# ST_LINK.net
KiCad netlist of a schematic drawn in Altium Designer
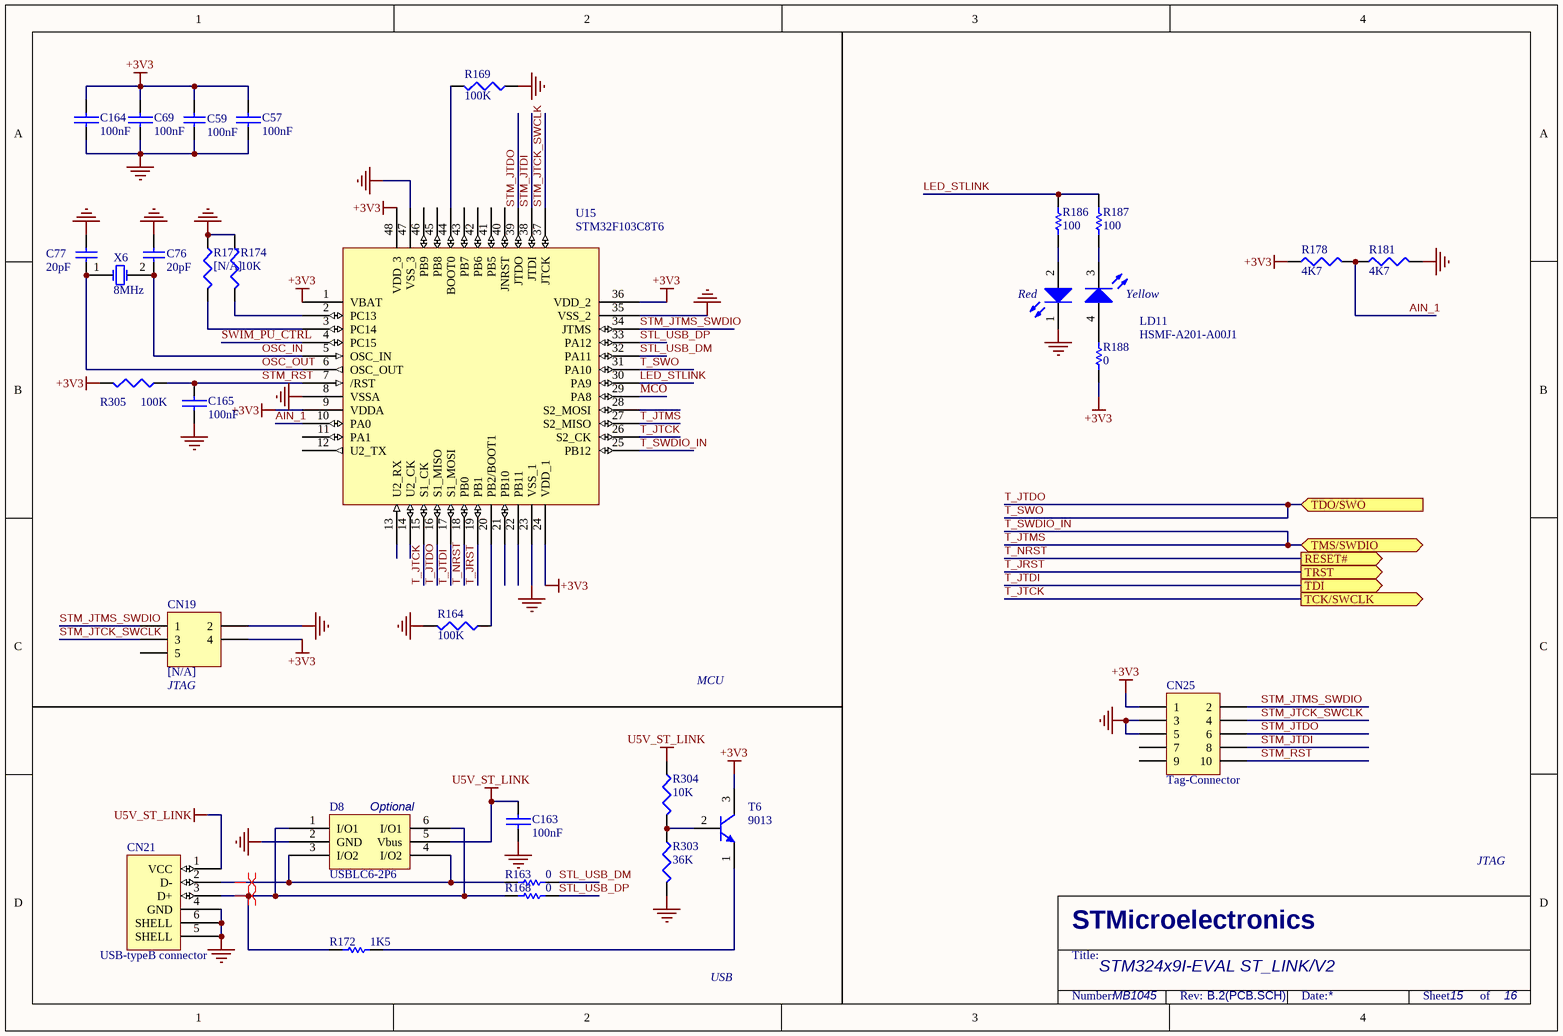
[diagram p0: ST_LINK.SCHDOC]

(export (version "E")
  (design (tool "Eeschema 10.0.6"))
  (components
    (comp (ref "C57") (value "100nF") (footprint "0603C") (libsource (lib "*") (part "CAP")))
    (comp (ref "C59")
      (value "100nF")
      (footprint "0603C")
      (description "Capacitor")
      (fields (field (name "PUBLISHER") "Altium Limited"))
      (libsource (lib "*") (part "Cap"))
    )
    (comp (ref "C69") (value "100nF") (footprint "0603C") (libsource (lib "*") (part "CAP")))
    (comp (ref "C76")
      (value "20pF")
      (footprint "0603C")
      (description "Capacitor")
      (fields (field (name "PUBLISHER") "Altium Limited"))
      (libsource (lib "*") (part "Cap"))
    )
    (comp (ref "C77")
      (value "20pF")
      (footprint "0603C")
      (description "Capacitor")
      (fields (field (name "PUBLISHER") "Altium Limited"))
      (libsource (lib "*") (part "Cap"))
    )
    (comp (ref "C163")
      (value "100nF")
      (footprint "0603C")
      (description "Capacitor")
      (libsource (lib "") (part "CAP_1"))
    )
    (comp (ref "C164") (value "100nF") (footprint "0603C") (libsource (lib "*") (part "CAP")))
    (comp (ref "C165") (value "100nF") (footprint "0603C") (libsource (lib "*") (part "CAP")))
    (comp (ref "CN19")
      (value "[N/A]")
      (footprint "HDR_2X3-1_2R54-6")
      (description "Header, 3-Pin, Dual row")
      (fields (field (name "PUBLISHER") "Altium Limited"))
      (libsource (lib "Miscellaneous Connectors") (part "Header 3X2"))
    )
    (comp (ref "CN21")
      (value "USB-typeB connector")
      (footprint "USB-B")
      (libsource (lib "mb1045") (part "USB-typeB connector"))
    )
    (comp (ref "CN25")
      (value "Tag-Connector")
      (footprint "TC2050-IDC-FP")
      (description "Header, 6-Pin, Dual row")
      (fields (field (name "PUBLISHER") "Altium Limited"))
      (libsource (lib "mb1045") (part "Tag-Connector"))
    )
    (comp (ref "D8") (value "USBLC6-2P6") (footprint "SOT-563") (libsource (lib "mb1045") (part "USBLC6-2")))
    (comp (ref "LD11")
      (value "HSMF-A201-A00J1")
      (footprint "LED2_3528")
      (libsource (lib "MB819") (part "HSMF-A201-A00J1"))
    )
    (comp (ref "R163")
      (value "0")
      (footprint "0603R")
      (description "Resistor")
      (fields (field (name "PUBLISHER") "Altium Limited"))
      (libsource (lib "Miscellaneous Devices") (part "Res1"))
    )
    (comp (ref "R164") (value "100K") (footprint "0603R") (libsource (lib "*") (part "RES1")))
    (comp (ref "R168")
      (value "0")
      (footprint "0603R")
      (description "Resistor")
      (fields (field (name "PUBLISHER") "Altium Limited"))
      (libsource (lib "Miscellaneous Devices") (part "Res1"))
    )
    (comp (ref "R169") (value "100K") (footprint "0603R") (libsource (lib "*") (part "RES1")))
    (comp (ref "R172")
      (value "1K5")
      (footprint "0603R")
      (description "Resistor")
      (fields (field (name "PUBLISHER") "Altium Limited"))
      (libsource (lib "Miscellaneous Devices") (part "Res1"))
    )
    (comp (ref "R174") (value "10K") (footprint "0603R") (libsource (lib "*") (part "R")))
    (comp (ref "R177") (value "[N/A]") (footprint "0603R") (libsource (lib "*") (part "R")))
    (comp (ref "R178") (value "4K7") (footprint "0603R") (libsource (lib "*") (part "RES1")))
    (comp (ref "R181") (value "4K7") (footprint "0603R") (libsource (lib "*") (part "RES1")))
    (comp (ref "R186")
      (value "100")
      (footprint "0603R")
      (description "Resistor")
      (fields (field (name "PUBLISHER") "Altium Limited"))
      (libsource (lib "Miscellaneous Devices") (part "Res1"))
    )
    (comp (ref "R187")
      (value "100")
      (footprint "0603R")
      (description "Resistor")
      (fields (field (name "PUBLISHER") "Altium Limited"))
      (libsource (lib "Miscellaneous Devices") (part "Res1"))
    )
    (comp (ref "R188")
      (value "0")
      (footprint "0603R")
      (description "Resistor")
      (fields (field (name "PUBLISHER") "Altium Limited"))
      (libsource (lib "Miscellaneous Devices") (part "Res1"))
    )
    (comp (ref "R303") (value "36K") (footprint "0603R") (libsource (lib "*") (part "R")))
    (comp (ref "R304") (value "10K") (footprint "0603R") (libsource (lib "*") (part "R")))
    (comp (ref "R305") (value "100K") (footprint "0603R") (libsource (lib "*") (part "RES1")))
    (comp (ref "T6")
      (value "9013")
      (footprint "SOT23-213")
      (description "NPN Bipolar Transistor")
      (fields (field (name "PUBLISHER") "Altium Limited"))
      (libsource (lib "mb1045") (part "NPN"))
    )
    (comp (ref "U15")
      (value "STM32F103C8T6")
      (footprint "LQFP48_0R5_9X9")
      (libsource (lib "*") (part "STM32F10x(48pin)"))
    )
    (comp (ref "X6")
      (value "8MHz")
      (footprint "XTAL_2SM_12R7X4R7")
      (description "Crystal Oscillator")
      (fields (field (name "PUBLISHER") "Altium Limited"))
      (libsource (lib "*") (part "XTAL"))
    )
  )
  (nets
    (net (code "1") (name "+3V3") (class "Default")
      (node (ref "C164") (pin "2") (pinfunction "2_2") (pintype "passive"))
      (node (ref "C57") (pin "2") (pinfunction "2_2") (pintype "passive"))
      (node (ref "C59") (pin "1") (pinfunction "1_1") (pintype "passive"))
      (node (ref "C69") (pin "2") (pinfunction "2_2") (pintype "passive"))
      (node (ref "CN19") (pin "4") (pinfunction "4_4") (pintype "passive"))
      (node (ref "CN25") (pin "1") (pinfunction "1_1") (pintype "passive"))
      (node (ref "R178") (pin "1") (pinfunction "1_1") (pintype "passive"))
      (node (ref "R188") (pin "2") (pinfunction "2_2") (pintype "passive"))
      (node (ref "R305") (pin "2") (pinfunction "2_2") (pintype "passive"))
      (node (ref "T6") (pin "3") (pinfunction "C_3") (pintype "passive"))
      (node (ref "U15") (pin "1") (pinfunction "VBAT_1") (pintype "power_in"))
      (node (ref "U15") (pin "24") (pinfunction "VDD_1_24") (pintype "power_in"))
      (node (ref "U15") (pin "36") (pinfunction "VDD_2_36") (pintype "power_in"))
      (node (ref "U15") (pin "48") (pinfunction "VDD_3_48") (pintype "power_in"))
      (node (ref "U15") (pin "9") (pinfunction "VDDA_9") (pintype "power_in"))
    )
    (net (code "2") (name "/AIN_1") (class "Default")
      (node (ref "R178") (pin "2") (pinfunction "2_2") (pintype "passive"))
      (node (ref "R181") (pin "1") (pinfunction "1_1") (pintype "passive"))
      (node (ref "U15") (pin "10") (pinfunction "PA0_10") (pintype "bidirectional"))
    )
    (net (code "3") (name "/LED_STLINK") (class "Default")
      (node (ref "R186") (pin "1") (pinfunction "1_1") (pintype "passive"))
      (node (ref "R187") (pin "1") (pinfunction "1_1") (pintype "passive"))
      (node (ref "U15") (pin "30") (pinfunction "PA9_30") (pintype "bidirectional"))
    )
    (net (code "4") (name "/MCO") (class "Default")
      (node (ref "U15") (pin "29") (pinfunction "PA8_29") (pintype "bidirectional"))
    )
    (net (code "5") (name "/OSC_IN") (class "Default")
      (node (ref "C76") (pin "2") (pinfunction "2_2") (pintype "passive"))
      (node (ref "U15") (pin "5") (pinfunction "OSC_IN_5") (pintype "input"))
      (node (ref "X6") (pin "2") (pinfunction "OSC2_2") (pintype "passive"))
    )
    (net (code "6") (name "/OSC_OUT") (class "Default")
      (node (ref "C77") (pin "2") (pinfunction "2_2") (pintype "passive"))
      (node (ref "U15") (pin "6") (pinfunction "OSC_OUT_6") (pintype "output"))
      (node (ref "X6") (pin "1") (pinfunction "OSC1_1") (pintype "passive"))
    )
    (net (code "7") (name "/STL_USB_DM") (class "Default")
      (node (ref "R163") (pin "1") (pinfunction "1_1") (pintype "passive"))
      (node (ref "U15") (pin "32") (pinfunction "PA11_32") (pintype "bidirectional"))
    )
    (net (code "8") (name "/STL_USB_DP") (class "Default")
      (node (ref "R168") (pin "1") (pinfunction "1_1") (pintype "passive"))
      (node (ref "U15") (pin "33") (pinfunction "PA12_33") (pintype "bidirectional"))
    )
    (net (code "9") (name "/STM_JTCK_SWCLK") (class "Default")
      (node (ref "CN19") (pin "3") (pinfunction "3_3") (pintype "passive"))
      (node (ref "CN25") (pin "4") (pinfunction "4_4") (pintype "passive"))
      (node (ref "U15") (pin "37") (pinfunction "JTCK_37") (pintype "bidirectional"))
    )
    (net (code "10") (name "/STM_JTDI") (class "Default")
      (node (ref "CN25") (pin "8") (pinfunction "8_8") (pintype "passive"))
      (node (ref "U15") (pin "38") (pinfunction "JTDI_38") (pintype "bidirectional"))
    )
    (net (code "11") (name "/STM_JTDO") (class "Default")
      (node (ref "CN25") (pin "6") (pinfunction "6_6") (pintype "passive"))
      (node (ref "U15") (pin "39") (pinfunction "JTDO_39") (pintype "bidirectional"))
    )
    (net (code "12") (name "/STM_JTMS_SWDIO") (class "Default")
      (node (ref "CN19") (pin "1") (pinfunction "1_1") (pintype "passive"))
      (node (ref "CN25") (pin "2") (pinfunction "2_2") (pintype "passive"))
      (node (ref "U15") (pin "34") (pinfunction "JTMS_34") (pintype "bidirectional"))
    )
    (net (code "13") (name "/STM_RST") (class "Default")
      (node (ref "C165") (pin "2") (pinfunction "2_2") (pintype "passive"))
      (node (ref "CN25") (pin "10") (pinfunction "10_10") (pintype "passive"))
      (node (ref "R305") (pin "1") (pinfunction "1_1") (pintype "passive"))
      (node (ref "U15") (pin "7") (pinfunction "/RST_7") (pintype "input"))
    )
    (net (code "14") (name "/SWIM_PU_CTRL") (class "Default")
      (node (ref "U15") (pin "4") (pinfunction "PC15_4") (pintype "bidirectional"))
    )
    (net (code "15") (name "/T_JRST") (class "Default")
      (node (ref "U15") (pin "19") (pinfunction "PB1_19") (pintype "bidirectional"))
    )
    (net (code "16") (name "/T_JTCK") (class "Default")
      (node (ref "U15") (pin "15") (pinfunction "S1_CK_15") (pintype "bidirectional"))
      (node (ref "U15") (pin "26") (pinfunction "S2_CK_26") (pintype "bidirectional"))
    )
    (net (code "17") (name "/T_JTDI") (class "Default")
      (node (ref "U15") (pin "17") (pinfunction "S1_MOSI_17") (pintype "bidirectional"))
    )
    (net (code "18") (name "/T_JTDO") (class "Default")
      (node (ref "U15") (pin "16") (pinfunction "S1_MISO_16") (pintype "bidirectional"))
      (node (ref "U15") (pin "31") (pinfunction "PA10_31") (pintype "bidirectional"))
    )
    (net (code "19") (name "/T_JTMS") (class "Default")
      (node (ref "U15") (pin "25") (pinfunction "PB12_25") (pintype "bidirectional"))
      (node (ref "U15") (pin "27") (pinfunction "S2_MISO_27") (pintype "bidirectional"))
    )
    (net (code "20") (name "/T_NRST") (class "Default")
      (node (ref "U15") (pin "18") (pinfunction "PB0_18") (pintype "bidirectional"))
    )
    (net (code "21") (name "GND") (class "Default")
      (node (ref "C163") (pin "2") (pinfunction "2_2") (pintype "passive"))
      (node (ref "C164") (pin "1") (pinfunction "1_1") (pintype "passive"))
      (node (ref "C165") (pin "1") (pinfunction "1_1") (pintype "passive"))
      (node (ref "C57") (pin "1") (pinfunction "1_1") (pintype "passive"))
      (node (ref "C59") (pin "2") (pinfunction "2_2") (pintype "passive"))
      (node (ref "C69") (pin "1") (pinfunction "1_1") (pintype "passive"))
      (node (ref "C76") (pin "1") (pinfunction "1_1") (pintype "passive"))
      (node (ref "C77") (pin "1") (pinfunction "1_1") (pintype "passive"))
      (node (ref "CN19") (pin "2") (pinfunction "2_2") (pintype "passive"))
      (node (ref "CN21") (pin "4") (pinfunction "GND_4") (pintype "passive"))
      (node (ref "CN21") (pin "5") (pinfunction "SHELL_5") (pintype "power_in"))
      (node (ref "CN21") (pin "6") (pinfunction "SHELL_6") (pintype "power_in"))
      (node (ref "CN25") (pin "3") (pinfunction "3_3") (pintype "passive"))
      (node (ref "CN25") (pin "5") (pinfunction "5_5") (pintype "passive"))
      (node (ref "D8") (pin "2") (pinfunction "GND_2") (pintype "passive"))
      (node (ref "LD11") (pin "1") (pinfunction "RED_cathode_1") (pintype "passive"))
      (node (ref "R164") (pin "2") (pinfunction "2_2") (pintype "passive"))
      (node (ref "R169") (pin "1") (pinfunction "1_1") (pintype "passive"))
      (node (ref "R174") (pin "1") (pinfunction "1_1") (pintype "passive"))
      (node (ref "R177") (pin "1") (pinfunction "1_1") (pintype "passive"))
      (node (ref "R181") (pin "2") (pinfunction "2_2") (pintype "passive"))
      (node (ref "R303") (pin "2") (pinfunction "2_2") (pintype "passive"))
      (node (ref "U15") (pin "23") (pinfunction "VSS_1_23") (pintype "passive"))
      (node (ref "U15") (pin "35") (pinfunction "VSS_2_35") (pintype "passive"))
      (node (ref "U15") (pin "47") (pinfunction "VSS_3_47") (pintype "passive"))
      (node (ref "U15") (pin "8") (pinfunction "VSSA_8") (pintype "passive"))
    )
    (net (code "22") (name "Net-(CN21-D+)") (class "Default")
      (node (ref "CN21") (pin "3") (pinfunction "D+_3") (pintype "bidirectional"))
      (node (ref "D8") (pin "1") (pinfunction "I/O1_1") (pintype "passive"))
      (node (ref "D8") (pin "6") (pinfunction "I/O1_6") (pintype "passive"))
      (node (ref "R168") (pin "2") (pinfunction "2_2") (pintype "passive"))
      (node (ref "R172") (pin "2") (pinfunction "2_2") (pintype "passive"))
    )
    (net (code "23") (name "Net-(CN21-D-)") (class "Default")
      (node (ref "CN21") (pin "2") (pinfunction "D-_2") (pintype "bidirectional"))
      (node (ref "D8") (pin "3") (pinfunction "I/O2_3") (pintype "passive"))
      (node (ref "D8") (pin "4") (pinfunction "I/O2_4") (pintype "passive"))
      (node (ref "R163") (pin "2") (pinfunction "2_2") (pintype "passive"))
    )
    (net (code "24") (name "Net-(LD11-Red_anode)") (class "Default")
      (node (ref "LD11") (pin "2") (pinfunction "Red_anode_2") (pintype "passive"))
      (node (ref "R186") (pin "2") (pinfunction "2_2") (pintype "passive"))
    )
    (net (code "25") (name "Net-(LD11-YellowGreen_anode)") (class "Default")
      (node (ref "LD11") (pin "4") (pinfunction "YellowGreen_anode_4") (pintype "passive"))
      (node (ref "R188") (pin "1") (pinfunction "1_1") (pintype "passive"))
    )
    (net (code "26") (name "Net-(LD11-YellowGreen_cathode)") (class "Default")
      (node (ref "LD11") (pin "3") (pinfunction "YellowGreen_cathode_3") (pintype "passive"))
      (node (ref "R187") (pin "2") (pinfunction "2_2") (pintype "passive"))
    )
    (net (code "27") (name "Net-(T6-B)") (class "Default")
      (node (ref "R303") (pin "1") (pinfunction "1_1") (pintype "passive"))
      (node (ref "R304") (pin "2") (pinfunction "2_2") (pintype "passive"))
      (node (ref "T6") (pin "2") (pinfunction "B_2") (pintype "passive"))
    )
    (net (code "28") (name "Net-(T6-E)") (class "Default")
      (node (ref "R172") (pin "1") (pinfunction "1_1") (pintype "passive"))
      (node (ref "T6") (pin "1") (pinfunction "E_1") (pintype "passive"))
    )
    (net (code "29") (name "Net-(U15-BOOT0)") (class "Default")
      (node (ref "R169") (pin "2") (pinfunction "2_2") (pintype "passive"))
      (node (ref "U15") (pin "44") (pinfunction "BOOT0_44") (pintype "bidirectional"))
    )
    (net (code "30") (name "Net-(U15-PB2{slash}BOOT1)") (class "Default")
      (node (ref "R164") (pin "1") (pinfunction "1_1") (pintype "passive"))
      (node (ref "U15") (pin "20") (pinfunction "PB2/BOOT1_20") (pintype "passive"))
    )
    (net (code "31") (name "Net-(U15-PC13)") (class "Default")
      (node (ref "R174") (pin "2") (pinfunction "2_2") (pintype "passive"))
      (node (ref "U15") (pin "2") (pinfunction "PC13_2") (pintype "bidirectional"))
    )
    (net (code "32") (name "Net-(U15-PC14)") (class "Default")
      (node (ref "R177") (pin "2") (pinfunction "2_2") (pintype "passive"))
      (node (ref "U15") (pin "3") (pinfunction "PC14_3") (pintype "bidirectional"))
    )
    (net (code "33") (name "U5V_ST_LINK") (class "Default")
      (node (ref "C163") (pin "1") (pinfunction "1_1") (pintype "passive"))
      (node (ref "CN21") (pin "1") (pinfunction "VCC_1") (pintype "bidirectional"))
      (node (ref "D8") (pin "5") (pinfunction "Vbus_5") (pintype "passive"))
      (node (ref "R304") (pin "1") (pinfunction "1_1") (pintype "passive"))
    )
    (net (code "34") (name "unconnected-(CN19-Pad5)") (class "Default")
      (node (ref "CN19") (pin "5") (pinfunction "5_5") (pintype "passive"))
    )
    (net (code "35") (name "unconnected-(CN25-Pad7)") (class "Default")
      (node (ref "CN25") (pin "7") (pinfunction "7_7") (pintype "passive"))
    )
    (net (code "36") (name "unconnected-(CN25-Pad9)") (class "Default")
      (node (ref "CN25") (pin "9") (pinfunction "9_9") (pintype "passive"))
    )
    (net (code "37") (name "unconnected-(U15-JNRST-Pad40)") (class "Default")
      (node (ref "U15") (pin "40") (pinfunction "JNRST_40") (pintype "bidirectional"))
    )
    (net (code "38") (name "unconnected-(U15-PA1-Pad11)") (class "Default")
      (node (ref "U15") (pin "11") (pinfunction "PA1_11") (pintype "bidirectional"))
    )
    (net (code "39") (name "unconnected-(U15-PB5-Pad41)") (class "Default")
      (node (ref "U15") (pin "41") (pinfunction "PB5_41") (pintype "bidirectional"))
    )
    (net (code "40") (name "unconnected-(U15-PB6-Pad42)") (class "Default")
      (node (ref "U15") (pin "42") (pinfunction "PB6_42") (pintype "bidirectional"))
    )
    (net (code "41") (name "unconnected-(U15-PB7-Pad43)") (class "Default")
      (node (ref "U15") (pin "43") (pinfunction "PB7_43") (pintype "bidirectional"))
    )
    (net (code "42") (name "unconnected-(U15-PB8-Pad45)") (class "Default")
      (node (ref "U15") (pin "45") (pinfunction "PB8_45") (pintype "bidirectional"))
    )
    (net (code "43") (name "unconnected-(U15-PB9-Pad46)") (class "Default")
      (node (ref "U15") (pin "46") (pinfunction "PB9_46") (pintype "bidirectional"))
    )
    (net (code "44") (name "unconnected-(U15-PB10-Pad21)") (class "Default")
      (node (ref "U15") (pin "21") (pinfunction "PB10_21") (pintype "bidirectional"))
    )
    (net (code "45") (name "unconnected-(U15-PB11-Pad22)") (class "Default")
      (node (ref "U15") (pin "22") (pinfunction "PB11_22") (pintype "passive"))
    )
    (net (code "46") (name "unconnected-(U15-S2_MOSI-Pad28)") (class "Default")
      (node (ref "U15") (pin "28") (pinfunction "S2_MOSI_28") (pintype "bidirectional"))
    )
    (net (code "47") (name "unconnected-(U15-U2_CK-Pad14)") (class "Default")
      (node (ref "U15") (pin "14") (pinfunction "U2_CK_14") (pintype "bidirectional"))
    )
    (net (code "48") (name "unconnected-(U15-U2_RX-Pad13)") (class "Default")
      (node (ref "U15") (pin "13") (pinfunction "U2_RX_13") (pintype "input"))
    )
    (net (code "49") (name "unconnected-(U15-U2_TX-Pad12)") (class "Default")
      (node (ref "U15") (pin "12") (pinfunction "U2_TX_12") (pintype "output"))
    )
  )
)
